# LEDadapter00.net
KiCad netlist of a schematic drawn in EAGLE
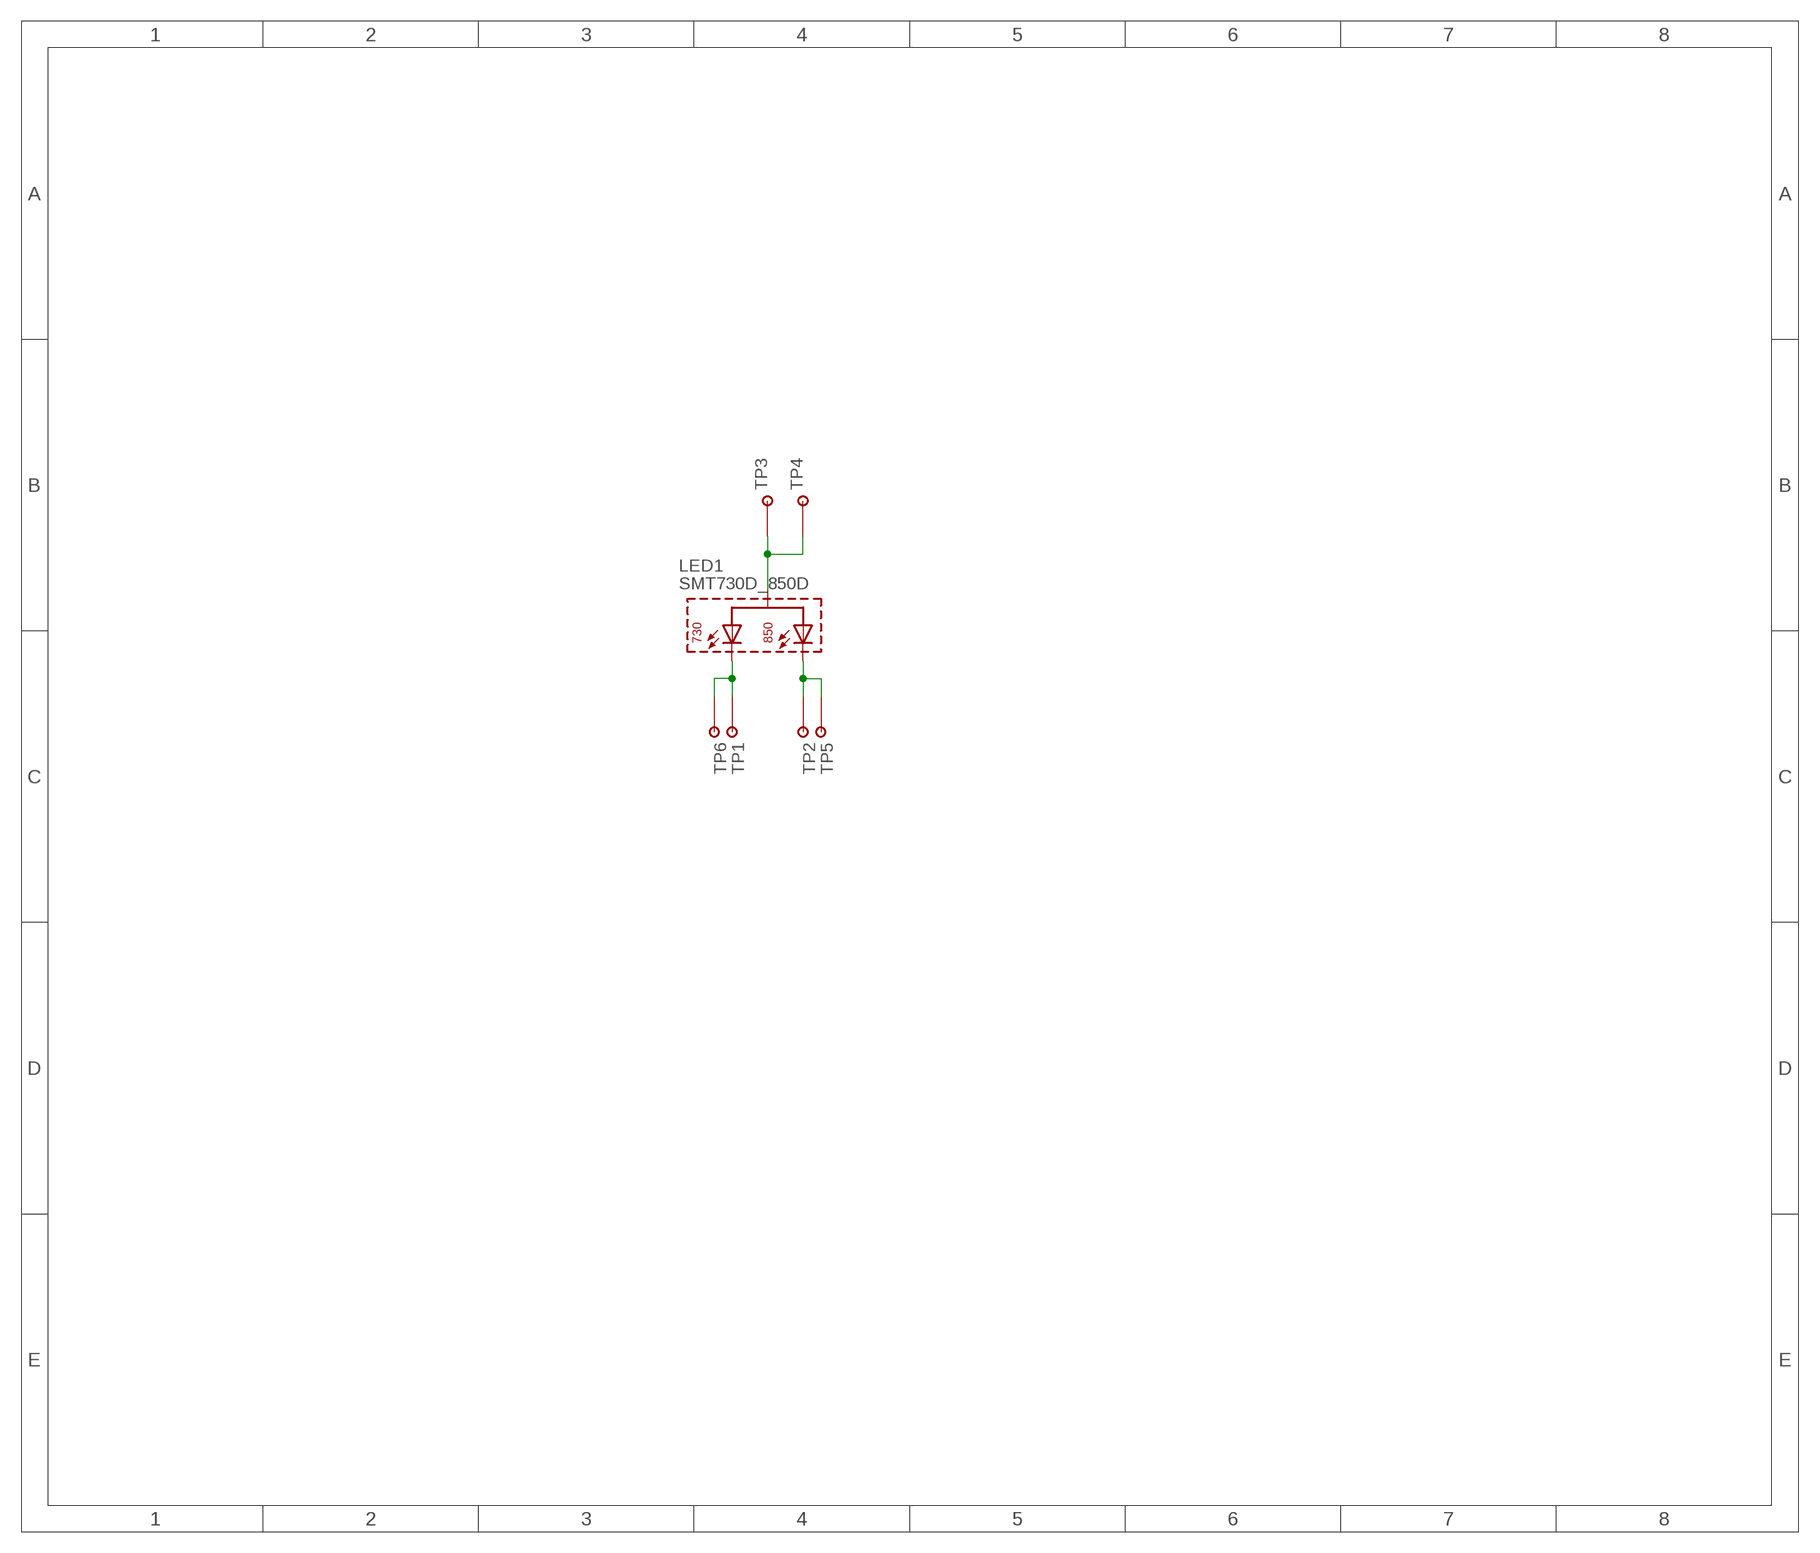
[diagram p0: schematic, sheet 1]

(export (version "E")
  (design (tool "Eeschema 10.0.6"))
  (components
    (comp (ref "LED1")
      (value "SMT730D_850D")
      (footprint "eagle-import:SMT730D_850D")
      (libsource (lib "eagle-import") (part "SMT730D_850D"))
    )
    (comp (ref "TP1")
      (value "TESTPOINT_PADMEDIUM")
      (footprint "eagle-import:TESTPAD_MEDIUM")
      (libsource (lib "eagle-import") (part "TESTPOINT_PADMEDIUM"))
    )
    (comp (ref "TP2")
      (value "TESTPOINT_PADMEDIUM")
      (footprint "eagle-import:TESTPAD_MEDIUM")
      (libsource (lib "eagle-import") (part "TESTPOINT_PADMEDIUM"))
    )
    (comp (ref "TP3")
      (value "TESTPOINT_PADMEDIUM")
      (footprint "eagle-import:TESTPAD_MEDIUM")
      (libsource (lib "eagle-import") (part "TESTPOINT_PADMEDIUM"))
    )
    (comp (ref "TP4")
      (value "TESTPOINT_PADMEDIUM")
      (footprint "eagle-import:TESTPAD_MEDIUM")
      (libsource (lib "eagle-import") (part "TESTPOINT_PADMEDIUM"))
    )
    (comp (ref "TP5")
      (value "TESTPOINT_PADMEDIUM")
      (footprint "eagle-import:TESTPAD_MEDIUM")
      (libsource (lib "eagle-import") (part "TESTPOINT_PADMEDIUM"))
    )
    (comp (ref "TP6")
      (value "TESTPOINT_PADMEDIUM")
      (footprint "eagle-import:TESTPAD_MEDIUM")
      (libsource (lib "eagle-import") (part "TESTPOINT_PADMEDIUM"))
    )
  )
  (nets
    (net (code "1") (name "Net-(LED1-PadA)") (class "Default")
      (node (ref "LED1") (pin "A") (pinfunction "A_A") (pintype "passive"))
      (node (ref "TP3") (pin "P$1") (pinfunction "P$1_P$1") (pintype "bidirectional"))
      (node (ref "TP4") (pin "P$1") (pinfunction "P$1_P$1") (pintype "bidirectional"))
    )
    (net (code "2") (name "Net-(LED1-PadC7)") (class "Default")
      (node (ref "LED1") (pin "C7") (pinfunction "C7_C7") (pintype "passive"))
      (node (ref "TP1") (pin "P$1") (pinfunction "P$1_P$1") (pintype "bidirectional"))
      (node (ref "TP6") (pin "P$1") (pinfunction "P$1_P$1") (pintype "bidirectional"))
    )
    (net (code "3") (name "Net-(LED1-PadC8)") (class "Default")
      (node (ref "LED1") (pin "C8") (pinfunction "C8_C8") (pintype "passive"))
      (node (ref "TP2") (pin "P$1") (pinfunction "P$1_P$1") (pintype "bidirectional"))
      (node (ref "TP5") (pin "P$1") (pinfunction "P$1_P$1") (pintype "bidirectional"))
    )
  )
)
